# PART6_Connectors.net
KiCad netlist of a schematic drawn in Altium Designer
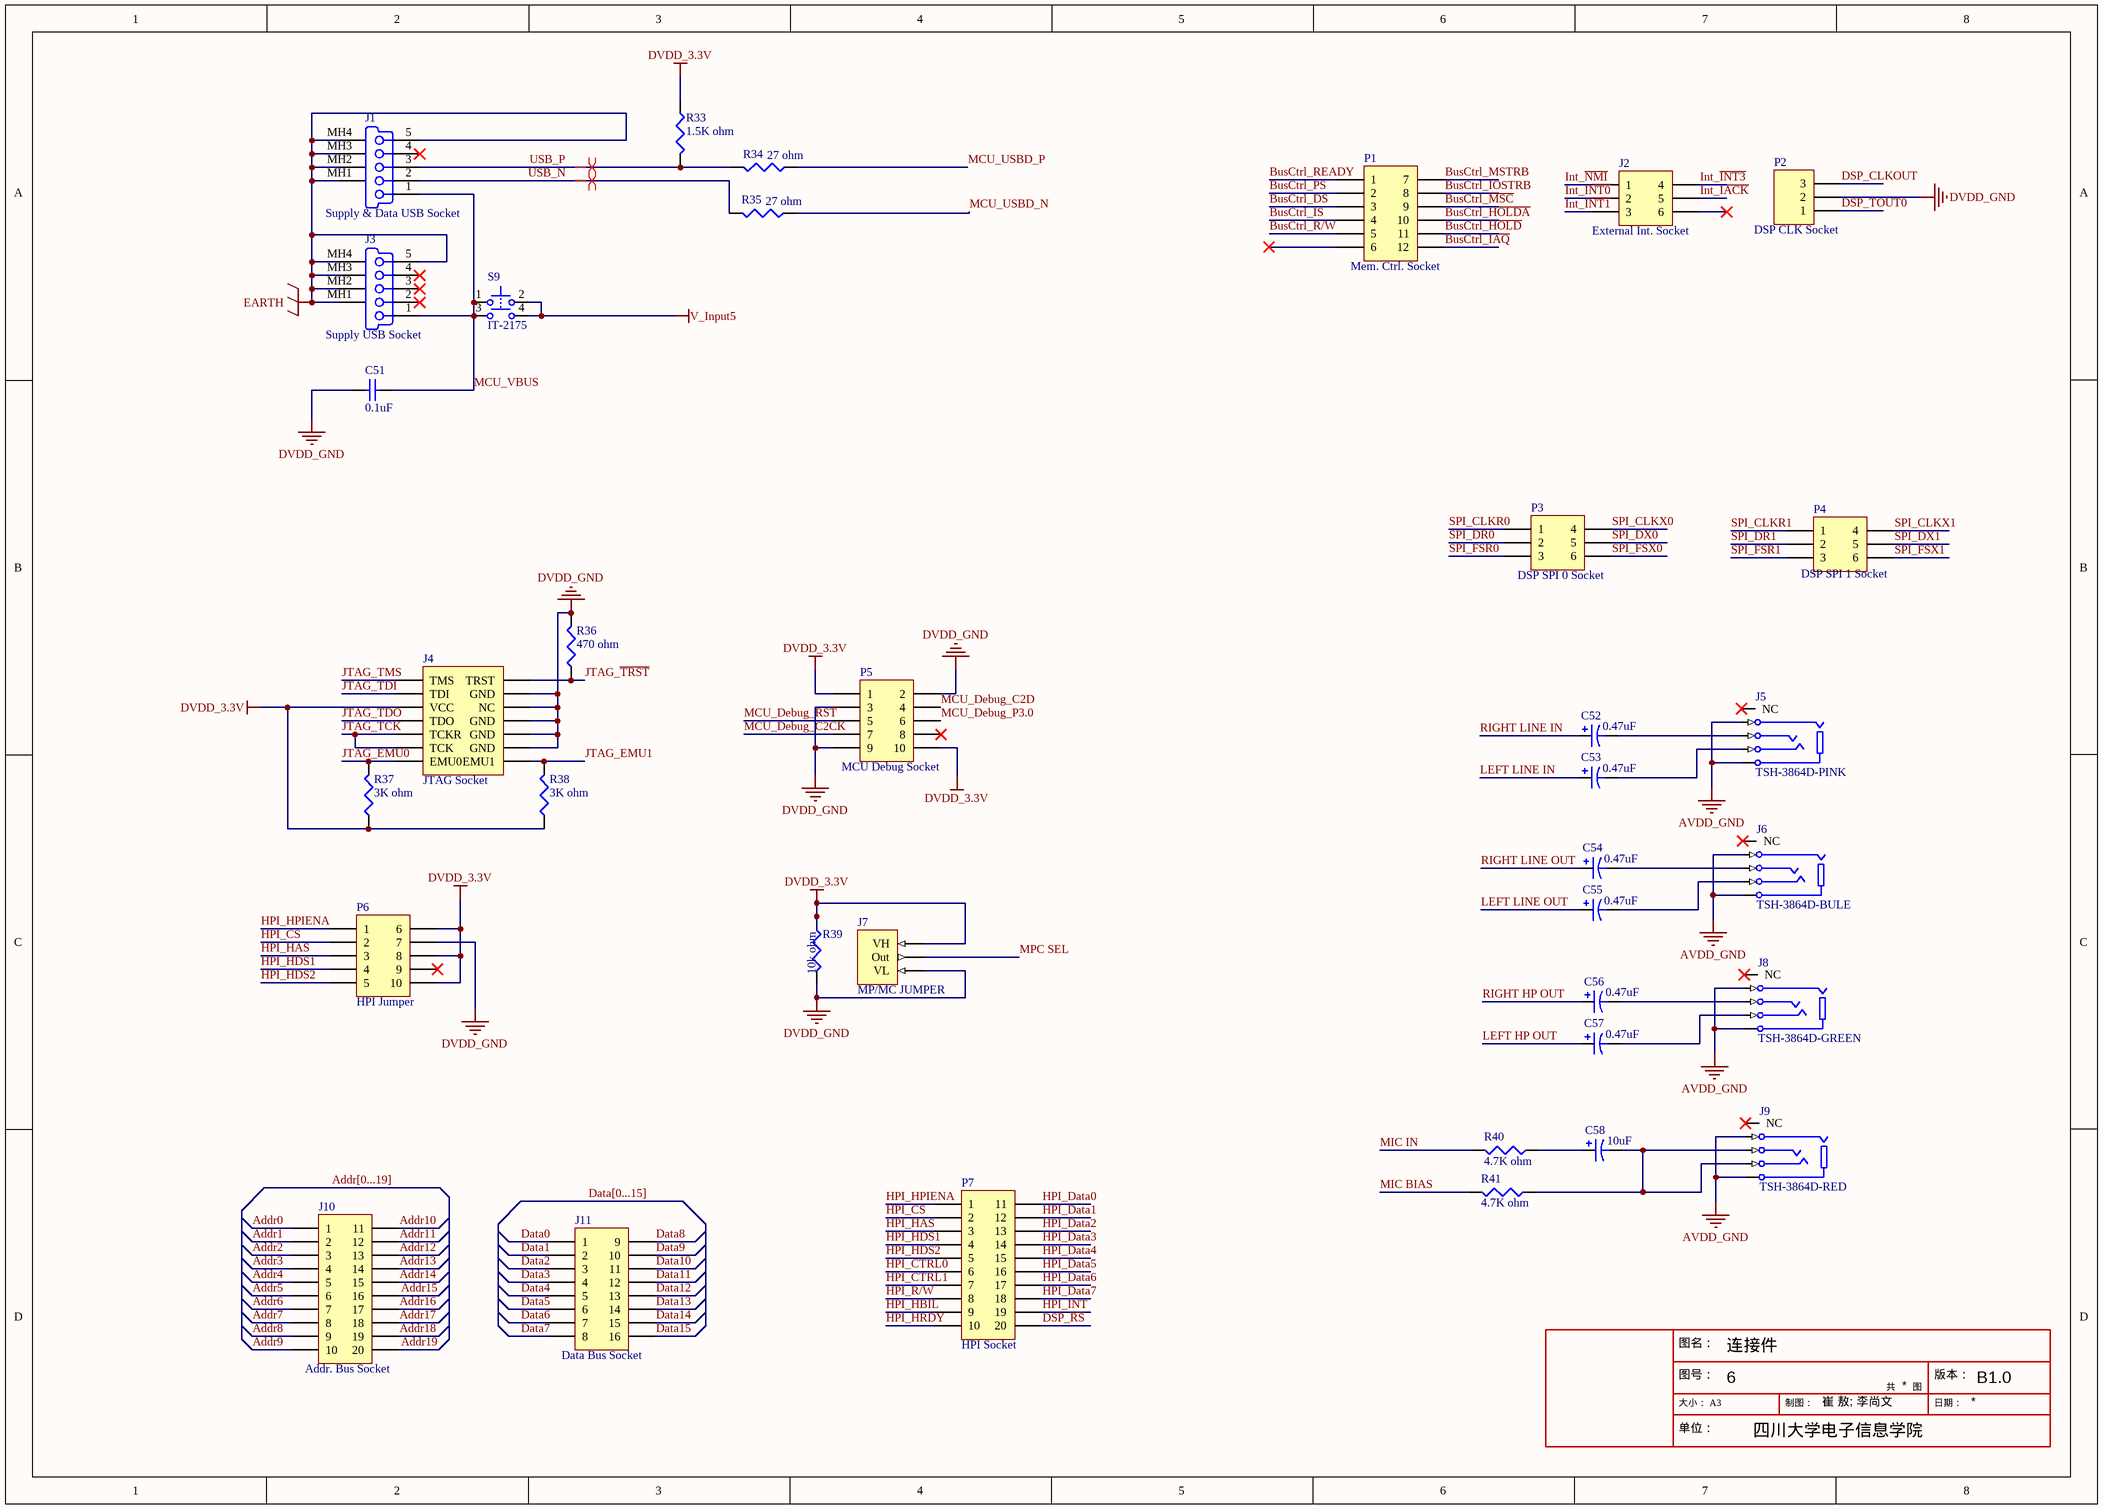
[diagram p0: PART6_Connectors.SchDoc]

(export (version "E")
  (design (tool "Eeschema 10.0.6"))
  (components
    (comp (ref "C51")
      (value "0.1uF")
      (footprint "1608[0603]")
      (description "贴片电容 1608")
      (fields (field (name "Comment") "Cap Semi") (field (name "PUBLISHER") "Altium Limited"))
      (libsource (lib "Miscellaneous Devices") (part "Cap Semi"))
    )
    (comp (ref "C52")
      (value "0.47uF")
      (footprint "C0805")
      (description "贴片钽电容 C0805")
      (fields (field (name "Comment") "Cap Tan") (field (name "PUBLISHER") "Altium Limited"))
      (libsource (lib "Miscellaneous Devices") (part "Cap Pol3"))
    )
    (comp (ref "C53")
      (value "0.47uF")
      (footprint "C0805")
      (description "贴片钽电容 C0805")
      (fields (field (name "Comment") "Cap Tan") (field (name "PUBLISHER") "Altium Limited"))
      (libsource (lib "Miscellaneous Devices") (part "Cap Pol3"))
    )
    (comp (ref "C54")
      (value "0.47uF")
      (footprint "C0805")
      (description "贴片钽电容 C0805")
      (fields (field (name "Comment") "Cap Tan") (field (name "PUBLISHER") "Altium Limited"))
      (libsource (lib "Miscellaneous Devices") (part "Cap Pol3"))
    )
    (comp (ref "C55")
      (value "0.47uF")
      (footprint "C0805")
      (description "贴片钽电容 C0805")
      (fields (field (name "Comment") "Cap Tan") (field (name "PUBLISHER") "Altium Limited"))
      (libsource (lib "Miscellaneous Devices") (part "Cap Pol3"))
    )
    (comp (ref "C56")
      (value "0.47uF")
      (footprint "C0805")
      (description "贴片钽电容 C0805")
      (fields (field (name "Comment") "Cap Tan") (field (name "PUBLISHER") "Altium Limited"))
      (libsource (lib "Miscellaneous Devices") (part "Cap Pol3"))
    )
    (comp (ref "C57")
      (value "0.47uF")
      (footprint "C0805")
      (description "贴片钽电容 C0805")
      (fields (field (name "Comment") "Cap Tan") (field (name "PUBLISHER") "Altium Limited"))
      (libsource (lib "Miscellaneous Devices") (part "Cap Pol3"))
    )
    (comp (ref "C58")
      (value "10uF")
      (footprint "C0805")
      (description "贴片钽电容 C0805")
      (fields (field (name "Comment") "Cap Tan") (field (name "PUBLISHER") "Altium Limited"))
      (libsource (lib "Miscellaneous Devices") (part "Cap Pol3"))
    )
    (comp (ref "J1")
      (value "Supply & Data USB Socket")
      (footprint "481900001")
      (fields (field (name "PUBLISHER") "Altium Limited"))
      (libsource (lib "Molex Serial Bus Mini USB") (part "0481900001"))
    )
    (comp (ref "J2")
      (value "External Int. Socket")
      (footprint "HDR2X3_CEN")
      (description "Header, 3-Pin, Dual row")
      (fields (field (name "PUBLISHER") "Altium Limited"))
      (libsource (lib "Miscellaneous Connectors") (part "Header 3X2A"))
    )
    (comp (ref "J3")
      (value "Supply USB Socket")
      (footprint "481900001")
      (fields (field (name "PUBLISHER") "Altium Limited"))
      (libsource (lib "Molex Serial Bus Mini USB") (part "0481900001"))
    )
    (comp (ref "J4")
      (value "JTAG Socket")
      (footprint "HDR2X7")
      (description "Header, 7-Pin, Dual row")
      (fields (field (name "PUBLISHER") "Altium Limited"))
      (libsource (lib "TMS320VC5401") (part "JTAG 14PIN CONN"))
    )
    (comp (ref "J5")
      (value "TSH-3864D-PINK")
      (footprint "PJ-386D")
      (description "Phone Jack, PJ-386D Series, Right Angle, SM, 4-Conductor Open Circuit")
      (fields (field (name "PUBLISHER") "Altium Limited"))
      (libsource (lib "Contact Technology Phone Jack") (part "TSH-3864D"))
    )
    (comp (ref "J6")
      (value "TSH-3864D-BULE")
      (footprint "PJ-386D")
      (description "Phone Jack, PJ-386D Series, Right Angle, SM, 4-Conductor Open Circuit")
      (fields (field (name "PUBLISHER") "Altium Limited"))
      (libsource (lib "Contact Technology Phone Jack") (part "TSH-3864D"))
    )
    (comp (ref "J7")
      (value "MP/MC JUMPER")
      (footprint "HDR1X3")
      (description "Header, 3-Pin")
      (fields (field (name "PUBLISHER") "Altium Limited"))
      (libsource (lib "Miscellaneous Connectors") (part "Header 3"))
    )
    (comp (ref "J8")
      (value "TSH-3864D-GREEN")
      (footprint "PJ-386D")
      (description "Phone Jack, PJ-386D Series, Right Angle, SM, 4-Conductor Open Circuit")
      (fields (field (name "PUBLISHER") "Altium Limited"))
      (libsource (lib "Contact Technology Phone Jack") (part "TSH-3864D"))
    )
    (comp (ref "J9")
      (value "TSH-3864D-RED")
      (footprint "PJ-386D")
      (description "Phone Jack, PJ-386D Series, Right Angle, SM, 4-Conductor Open Circuit")
      (fields (field (name "PUBLISHER") "Altium Limited"))
      (libsource (lib "Contact Technology Phone Jack") (part "TSH-3864D"))
    )
    (comp (ref "J10")
      (value "Addr. Bus Socket")
      (footprint "HDR2X10_CEN")
      (description "Header, 10-Pin, Dual row")
      (fields (field (name "PUBLISHER") "Altium Limited"))
      (libsource (lib "Miscellaneous Connectors") (part "Header 10X2A"))
    )
    (comp (ref "J11")
      (value "Data Bus Socket")
      (footprint "HDR2X8_CEN")
      (description "Header, 8-Pin, Dual row")
      (fields (field (name "PUBLISHER") "Altium Limited"))
      (libsource (lib "Miscellaneous Connectors") (part "Header 8X2A"))
    )
    (comp (ref "P1")
      (value "Mem. Ctrl. Socket")
      (footprint "HDR2X6_CEN")
      (description "Header, 6-Pin, Dual row")
      (fields (field (name "PUBLISHER") "Altium Limited"))
      (libsource (lib "Miscellaneous Connectors") (part "Header 6X2A"))
    )
    (comp (ref "P2")
      (value "DSP CLK Socket")
      (footprint "HDR1X3")
      (description "Header, 3-Pin")
      (fields (field (name "PUBLISHER") "Altium Limited"))
      (libsource (lib "Miscellaneous Connectors") (part "Header 3"))
    )
    (comp (ref "P3")
      (value "DSP SPI 0 Socket")
      (footprint "HDR2X3_CEN")
      (description "Header, 3-Pin, Dual row")
      (fields (field (name "PUBLISHER") "Altium Limited"))
      (libsource (lib "Miscellaneous Connectors") (part "Header 3X2A"))
    )
    (comp (ref "P4")
      (value "DSP SPI 1 Socket")
      (footprint "HDR2X3_CEN")
      (description "Header, 3-Pin, Dual row")
      (fields (field (name "PUBLISHER") "Altium Limited"))
      (libsource (lib "Miscellaneous Connectors") (part "Header 3X2A"))
    )
    (comp (ref "P5")
      (value "MCU Debug Socket")
      (footprint "HDR2X5")
      (description "Header, 5-Pin, Dual row")
      (fields (field (name "PUBLISHER") "Altium Limited"))
      (libsource (lib "Miscellaneous Connectors") (part "Header 5X2"))
    )
    (comp (ref "P6")
      (value "HPI Jumper")
      (footprint "HDR2X5_CEN")
      (description "Header, 5-Pin, Dual row")
      (fields (field (name "PUBLISHER") "Altium Limited"))
      (libsource (lib "Miscellaneous Connectors") (part "Header 5X2A"))
    )
    (comp (ref "P7")
      (value "HPI Socket")
      (footprint "HDR2X10_CEN")
      (description "Header, 10-Pin, Dual row")
      (fields (field (name "PUBLISHER") "Altium Limited"))
      (libsource (lib "Miscellaneous Connectors") (part "Header 10X2A"))
    )
    (comp (ref "R33")
      (value "1.5K ohm")
      (footprint "J1-0603")
      (description "贴片电阻 0603")
      (fields (field (name "Comment") "Res3") (field (name "PUBLISHER") "Altium Limited"))
      (libsource (lib "Miscellaneous Devices") (part "Res3"))
    )
    (comp (ref "R34")
      (value "27 ohm")
      (footprint "J1-0603")
      (description "贴片电阻 0603")
      (fields (field (name "Comment") "Res3") (field (name "PUBLISHER") "Altium Limited"))
      (libsource (lib "Miscellaneous Devices") (part "Res3"))
    )
    (comp (ref "R35")
      (value "27 ohm")
      (footprint "J1-0603")
      (description "贴片电阻 0603")
      (fields (field (name "Comment") "Res3") (field (name "PUBLISHER") "Altium Limited"))
      (libsource (lib "Miscellaneous Devices") (part "Res3"))
    )
    (comp (ref "R36")
      (value "470 ohm")
      (footprint "J1-0603")
      (description "贴片电阻 0603")
      (fields (field (name "Comment") "Res3") (field (name "PUBLISHER") "Altium Limited"))
      (libsource (lib "Miscellaneous Devices") (part "Res3"))
    )
    (comp (ref "R37")
      (value "3K ohm")
      (footprint "J1-0603")
      (description "贴片电阻 0603")
      (fields (field (name "Comment") "Res3") (field (name "PUBLISHER") "Altium Limited"))
      (libsource (lib "Miscellaneous Devices") (part "Res3"))
    )
    (comp (ref "R38")
      (value "3K ohm")
      (footprint "J1-0603")
      (description "贴片电阻 0603")
      (fields (field (name "Comment") "Res3") (field (name "PUBLISHER") "Altium Limited"))
      (libsource (lib "Miscellaneous Devices") (part "Res3"))
    )
    (comp (ref "R39")
      (value "10k ohm")
      (footprint "J1-0603")
      (description "贴片电阻 0603")
      (fields (field (name "Comment") "Res3") (field (name "PUBLISHER") "Altium Limited"))
      (libsource (lib "Miscellaneous Devices") (part "Res3"))
    )
    (comp (ref "R40")
      (value "4.7K ohm")
      (footprint "J1-0603")
      (description "贴片电阻 0603")
      (fields (field (name "Comment") "Res3") (field (name "PUBLISHER") "Altium Limited"))
      (libsource (lib "Miscellaneous Devices") (part "Res3"))
    )
    (comp (ref "R41")
      (value "4.7K ohm")
      (footprint "J1-0603")
      (description "贴片电阻 0603")
      (fields (field (name "Comment") "Res3") (field (name "PUBLISHER") "Altium Limited"))
      (libsource (lib "Miscellaneous Devices") (part "Res3"))
    )
    (comp (ref "S9")
      (value "IT-2175")
      (footprint "IT-2175")
      (description "Tactile Switch, DPST; Thru-Hole; Vertical; Rating DC 12V, 50mA (max)")
      (fields (field (name "PUBLISHER") "Altium Limited"))
      (libsource (lib "IL Switch Push Button") (part "IT-2175"))
    )
  )
  (nets
    (net (code "3") (name "/Addr0") (class "Default")
      (node (ref "J10") (pin "1") (pinfunction "1_1") (pintype "passive"))
    )
    (net (code "4") (name "/Addr1") (class "Default")
      (node (ref "J10") (pin "2") (pinfunction "2_2") (pintype "passive"))
    )
    (net (code "5") (name "/Addr2") (class "Default")
      (node (ref "J10") (pin "3") (pinfunction "3_3") (pintype "passive"))
    )
    (net (code "6") (name "/Addr3") (class "Default")
      (node (ref "J10") (pin "4") (pinfunction "4_4") (pintype "passive"))
    )
    (net (code "7") (name "/Addr4") (class "Default")
      (node (ref "J10") (pin "5") (pinfunction "5_5") (pintype "passive"))
    )
    (net (code "8") (name "/Addr5") (class "Default")
      (node (ref "J10") (pin "6") (pinfunction "6_6") (pintype "passive"))
    )
    (net (code "9") (name "/Addr6") (class "Default")
      (node (ref "J10") (pin "7") (pinfunction "7_7") (pintype "passive"))
    )
    (net (code "10") (name "/Addr7") (class "Default")
      (node (ref "J10") (pin "8") (pinfunction "8_8") (pintype "passive"))
    )
    (net (code "11") (name "/Addr8") (class "Default")
      (node (ref "J10") (pin "9") (pinfunction "9_9") (pintype "passive"))
    )
    (net (code "12") (name "/Addr9") (class "Default")
      (node (ref "J10") (pin "10") (pinfunction "10_10") (pintype "passive"))
    )
    (net (code "13") (name "/Addr10") (class "Default")
      (node (ref "J10") (pin "11") (pinfunction "11_11") (pintype "passive"))
    )
    (net (code "14") (name "/Addr11") (class "Default")
      (node (ref "J10") (pin "12") (pinfunction "12_12") (pintype "passive"))
    )
    (net (code "15") (name "/Addr12") (class "Default")
      (node (ref "J10") (pin "13") (pinfunction "13_13") (pintype "passive"))
    )
    (net (code "16") (name "/Addr13") (class "Default")
      (node (ref "J10") (pin "14") (pinfunction "14_14") (pintype "passive"))
    )
    (net (code "17") (name "/Addr14") (class "Default")
      (node (ref "J10") (pin "15") (pinfunction "15_15") (pintype "passive"))
    )
    (net (code "18") (name "/Addr15") (class "Default")
      (node (ref "J10") (pin "16") (pinfunction "16_16") (pintype "passive"))
    )
    (net (code "19") (name "/Addr16") (class "Default")
      (node (ref "J10") (pin "17") (pinfunction "17_17") (pintype "passive"))
    )
    (net (code "20") (name "/Addr17") (class "Default")
      (node (ref "J10") (pin "18") (pinfunction "18_18") (pintype "passive"))
    )
    (net (code "21") (name "/Addr18") (class "Default")
      (node (ref "J10") (pin "19") (pinfunction "19_19") (pintype "passive"))
    )
    (net (code "22") (name "/Addr19") (class "Default")
      (node (ref "J10") (pin "20") (pinfunction "20_20") (pintype "passive"))
    )
    (net (code "23") (name "/BusCtrl_IOSTRB") (class "Default")
      (node (ref "P1") (pin "8") (pinfunction "8_8") (pintype "passive"))
    )
    (net (code "24") (name "/BusCtrl_MSTRB") (class "Default")
      (node (ref "P1") (pin "7") (pinfunction "7_7") (pintype "passive"))
    )
    (net (code "25") (name "/BusCtrl_READY") (class "Default")
      (node (ref "P1") (pin "1") (pinfunction "1_1") (pintype "passive"))
    )
    (net (code "26") (name "/BusCtrl_R{slash}~{W}") (class "Default")
      (node (ref "P1") (pin "5") (pinfunction "5_5") (pintype "passive"))
    )
    (net (code "27") (name "/BusCtrl_~{DS}") (class "Default")
      (node (ref "P1") (pin "3") (pinfunction "3_3") (pintype "passive"))
    )
    (net (code "28") (name "/BusCtrl_~{HOLDA}") (class "Default")
      (node (ref "P1") (pin "10") (pinfunction "10_10") (pintype "passive"))
    )
    (net (code "29") (name "/BusCtrl_~{HOLD}") (class "Default")
      (node (ref "P1") (pin "11") (pinfunction "11_11") (pintype "passive"))
    )
    (net (code "30") (name "/BusCtrl_~{IAQ}") (class "Default")
      (node (ref "P1") (pin "12") (pinfunction "12_12") (pintype "passive"))
    )
    (net (code "31") (name "/BusCtrl_~{IS}") (class "Default")
      (node (ref "P1") (pin "4") (pinfunction "4_4") (pintype "passive"))
    )
    (net (code "32") (name "/BusCtrl_~{MSC}") (class "Default")
      (node (ref "P1") (pin "9") (pinfunction "9_9") (pintype "passive"))
    )
    (net (code "33") (name "/BusCtrl_~{PS}") (class "Default")
      (node (ref "P1") (pin "2") (pinfunction "2_2") (pintype "passive"))
    )
    (net (code "34") (name "/DSP_CLKOUT") (class "Default")
      (node (ref "P2") (pin "3") (pinfunction "VH_3") (pintype "input"))
    )
    (net (code "35") (name "/DSP_TOUT0") (class "Default")
      (node (ref "P2") (pin "1") (pinfunction "VL_1") (pintype "input"))
    )
    (net (code "36") (name "/DSP_~{RS}") (class "Default")
      (node (ref "P7") (pin "20") (pinfunction "20_20") (pintype "passive"))
    )
    (net (code "37") (name "/Data0") (class "Default")
      (node (ref "J11") (pin "1") (pinfunction "1_1") (pintype "passive"))
    )
    (net (code "38") (name "/Data1") (class "Default")
      (node (ref "J11") (pin "2") (pinfunction "2_2") (pintype "passive"))
    )
    (net (code "39") (name "/Data2") (class "Default")
      (node (ref "J11") (pin "3") (pinfunction "3_3") (pintype "passive"))
    )
    (net (code "40") (name "/Data3") (class "Default")
      (node (ref "J11") (pin "4") (pinfunction "4_4") (pintype "passive"))
    )
    (net (code "41") (name "/Data4") (class "Default")
      (node (ref "J11") (pin "5") (pinfunction "5_5") (pintype "passive"))
    )
    (net (code "42") (name "/Data5") (class "Default")
      (node (ref "J11") (pin "6") (pinfunction "6_6") (pintype "passive"))
    )
    (net (code "43") (name "/Data6") (class "Default")
      (node (ref "J11") (pin "7") (pinfunction "7_7") (pintype "passive"))
    )
    (net (code "44") (name "/Data7") (class "Default")
      (node (ref "J11") (pin "8") (pinfunction "8_8") (pintype "passive"))
    )
    (net (code "45") (name "/Data8") (class "Default")
      (node (ref "J11") (pin "9") (pinfunction "9_9") (pintype "passive"))
    )
    (net (code "46") (name "/Data9") (class "Default")
      (node (ref "J11") (pin "10") (pinfunction "10_10") (pintype "passive"))
    )
    (net (code "47") (name "/Data10") (class "Default")
      (node (ref "J11") (pin "11") (pinfunction "11_11") (pintype "passive"))
    )
    (net (code "48") (name "/Data11") (class "Default")
      (node (ref "J11") (pin "12") (pinfunction "12_12") (pintype "passive"))
    )
    (net (code "49") (name "/Data12") (class "Default")
      (node (ref "J11") (pin "13") (pinfunction "13_13") (pintype "passive"))
    )
    (net (code "50") (name "/Data13") (class "Default")
      (node (ref "J11") (pin "14") (pinfunction "14_14") (pintype "passive"))
    )
    (net (code "51") (name "/Data14") (class "Default")
      (node (ref "J11") (pin "15") (pinfunction "15_15") (pintype "passive"))
    )
    (net (code "52") (name "/Data15") (class "Default")
      (node (ref "J11") (pin "16") (pinfunction "16_16") (pintype "passive"))
    )
    (net (code "53") (name "/HPI_CTRL0") (class "Default")
      (node (ref "P7") (pin "6") (pinfunction "6_6") (pintype "passive"))
    )
    (net (code "54") (name "/HPI_CTRL1") (class "Default")
      (node (ref "P7") (pin "7") (pinfunction "7_7") (pintype "passive"))
    )
    (net (code "55") (name "/HPI_Data0") (class "Default")
      (node (ref "P7") (pin "11") (pinfunction "11_11") (pintype "passive"))
    )
    (net (code "56") (name "/HPI_Data1") (class "Default")
      (node (ref "P7") (pin "12") (pinfunction "12_12") (pintype "passive"))
    )
    (net (code "57") (name "/HPI_Data2") (class "Default")
      (node (ref "P7") (pin "13") (pinfunction "13_13") (pintype "passive"))
    )
    (net (code "58") (name "/HPI_Data3") (class "Default")
      (node (ref "P7") (pin "14") (pinfunction "14_14") (pintype "passive"))
    )
    (net (code "59") (name "/HPI_Data4") (class "Default")
      (node (ref "P7") (pin "15") (pinfunction "15_15") (pintype "passive"))
    )
    (net (code "60") (name "/HPI_Data5") (class "Default")
      (node (ref "P7") (pin "16") (pinfunction "16_16") (pintype "passive"))
    )
    (net (code "61") (name "/HPI_Data6") (class "Default")
      (node (ref "P7") (pin "17") (pinfunction "17_17") (pintype "passive"))
    )
    (net (code "62") (name "/HPI_Data7") (class "Default")
      (node (ref "P7") (pin "18") (pinfunction "18_18") (pintype "passive"))
    )
    (net (code "63") (name "/HPI_HBIL") (class "Default")
      (node (ref "P7") (pin "9") (pinfunction "9_9") (pintype "passive"))
    )
    (net (code "64") (name "/HPI_HPIENA") (class "Default")
      (node (ref "P6") (pin "1") (pinfunction "1_1") (pintype "passive"))
      (node (ref "P7") (pin "1") (pinfunction "1_1") (pintype "passive"))
    )
    (net (code "65") (name "/HPI_HRDY") (class "Default")
      (node (ref "P7") (pin "10") (pinfunction "10_10") (pintype "passive"))
    )
    (net (code "66") (name "/HPI_INT") (class "Default")
      (node (ref "P7") (pin "19") (pinfunction "19_19") (pintype "passive"))
    )
    (net (code "67") (name "/HPI_R{slash}~{W}") (class "Default")
      (node (ref "P7") (pin "8") (pinfunction "8_8") (pintype "passive"))
    )
    (net (code "68") (name "/HPI_~{CS}") (class "Default")
      (node (ref "P6") (pin "2") (pinfunction "2_2") (pintype "passive"))
      (node (ref "P7") (pin "2") (pinfunction "2_2") (pintype "passive"))
    )
    (net (code "69") (name "/HPI_~{HAS}") (class "Default")
      (node (ref "P6") (pin "3") (pinfunction "3_3") (pintype "passive"))
      (node (ref "P7") (pin "3") (pinfunction "3_3") (pintype "passive"))
    )
    (net (code "70") (name "/HPI_~{HDS1}") (class "Default")
      (node (ref "P6") (pin "4") (pinfunction "4_4") (pintype "passive"))
      (node (ref "P7") (pin "4") (pinfunction "4_4") (pintype "passive"))
    )
    (net (code "71") (name "/HPI_~{HDS2}") (class "Default")
      (node (ref "P6") (pin "5") (pinfunction "5_5") (pintype "passive"))
      (node (ref "P7") (pin "5") (pinfunction "5_5") (pintype "passive"))
    )
    (net (code "72") (name "/Int_~{IACK}") (class "Default")
      (node (ref "J2") (pin "5") (pinfunction "5_5") (pintype "passive"))
    )
    (net (code "73") (name "/Int_~{INT0}") (class "Default")
      (node (ref "J2") (pin "2") (pinfunction "2_2") (pintype "passive"))
    )
    (net (code "74") (name "/Int_~{INT1}") (class "Default")
      (node (ref "J2") (pin "3") (pinfunction "3_3") (pintype "passive"))
    )
    (net (code "75") (name "/Int_~{INT3}") (class "Default")
      (node (ref "J2") (pin "4") (pinfunction "4_4") (pintype "passive"))
    )
    (net (code "76") (name "/Int_~{NMI}") (class "Default")
      (node (ref "J2") (pin "1") (pinfunction "1_1") (pintype "passive"))
    )
    (net (code "77") (name "/JTAG_EMU0") (class "Default")
      (node (ref "J4") (pin "13") (pinfunction "EMU0_13") (pintype "passive"))
      (node (ref "R37") (pin "2") (pinfunction "2_2") (pintype "passive"))
    )
    (net (code "78") (name "/JTAG_EMU1") (class "Default")
      (node (ref "J4") (pin "14") (pinfunction "EMU1_14") (pintype "passive"))
      (node (ref "R38") (pin "2") (pinfunction "2_2") (pintype "passive"))
    )
    (net (code "79") (name "/JTAG_TCK") (class "Default")
      (node (ref "J4") (pin "11") (pinfunction "TCK_11") (pintype "passive"))
      (node (ref "J4") (pin "9") (pinfunction "TCKR_9") (pintype "passive"))
    )
    (net (code "80") (name "/JTAG_TDI") (class "Default")
      (node (ref "J4") (pin "3") (pinfunction "TDI_3") (pintype "passive"))
    )
    (net (code "81") (name "/JTAG_TDO") (class "Default")
      (node (ref "J4") (pin "7") (pinfunction "TDO_7") (pintype "passive"))
    )
    (net (code "82") (name "/JTAG_TMS") (class "Default")
      (node (ref "J4") (pin "1") (pinfunction "TMS_1") (pintype "passive"))
    )
    (net (code "83") (name "/JTAG_~{TRST}") (class "Default")
      (node (ref "J4") (pin "2") (pinfunction "TRST_2") (pintype "passive"))
      (node (ref "R36") (pin "1") (pinfunction "1_1") (pintype "passive"))
    )
    (net (code "84") (name "/LEFT HP OUT") (class "Default")
      (node (ref "C57") (pin "1") (pinfunction "1_1") (pintype "passive"))
    )
    (net (code "85") (name "/LEFT LINE IN") (class "Default")
      (node (ref "C53") (pin "1") (pinfunction "1_1") (pintype "passive"))
    )
    (net (code "86") (name "/LEFT LINE OUT") (class "Default")
      (node (ref "C55") (pin "1") (pinfunction "1_1") (pintype "passive"))
    )
    (net (code "87") (name "/MCU_Debug_C2CK") (class "Default")
      (node (ref "P5") (pin "7") (pinfunction "7_7") (pintype "passive"))
    )
    (net (code "88") (name "/MCU_Debug_C2D") (class "Default")
      (node (ref "P5") (pin "4") (pinfunction "4_4") (pintype "passive"))
    )
    (net (code "89") (name "/MCU_Debug_P3.0") (class "Default")
      (node (ref "P5") (pin "6") (pinfunction "6_6") (pintype "passive"))
    )
    (net (code "90") (name "/MCU_Debug_~{RST}") (class "Default")
      (node (ref "P5") (pin "5") (pinfunction "5_5") (pintype "passive"))
    )
    (net (code "91") (name "/MCU_USBD_N") (class "Default")
      (node (ref "R35") (pin "1") (pinfunction "1_1") (pintype "passive"))
    )
    (net (code "92") (name "/MCU_USBD_P") (class "Default")
      (node (ref "R34") (pin "1") (pinfunction "1_1") (pintype "passive"))
    )
    (net (code "93") (name "/MCU_VBUS") (class "Default")
      (node (ref "C51") (pin "2") (pinfunction "2_2") (pintype "passive"))
      (node (ref "J1") (pin "1") (pinfunction "V_BUS_(5V)_1") (pintype "passive"))
      (node (ref "J3") (pin "1") (pinfunction "V_BUS_(5V)_1") (pintype "passive"))
      (node (ref "S9") (pin "1") (pinfunction "1_1") (pintype "passive"))
      (node (ref "S9") (pin "3") (pinfunction "3_3") (pintype "passive"))
    )
    (net (code "94") (name "/MIC BIAS") (class "Default")
      (node (ref "R41") (pin "2") (pinfunction "2_2") (pintype "passive"))
    )
    (net (code "95") (name "/MIC IN") (class "Default")
      (node (ref "R40") (pin "2") (pinfunction "2_2") (pintype "passive"))
    )
    (net (code "96") (name "/MPC SEL") (class "Default")
      (node (ref "J7") (pin "2") (pinfunction "Out_2") (pintype "output"))
    )
    (net (code "97") (name "/RIGHT HP OUT") (class "Default")
      (node (ref "C56") (pin "1") (pinfunction "1_1") (pintype "passive"))
    )
    (net (code "98") (name "/RIGHT LINE IN") (class "Default")
      (node (ref "C52") (pin "1") (pinfunction "1_1") (pintype "passive"))
    )
    (net (code "99") (name "/RIGHT LINE OUT") (class "Default")
      (node (ref "C54") (pin "1") (pinfunction "1_1") (pintype "passive"))
    )
    (net (code "100") (name "/SPI_CLKR0") (class "Default")
      (node (ref "P3") (pin "1") (pinfunction "1_1") (pintype "passive"))
    )
    (net (code "101") (name "/SPI_CLKR1") (class "Default")
      (node (ref "P4") (pin "1") (pinfunction "1_1") (pintype "passive"))
    )
    (net (code "102") (name "/SPI_CLKX0") (class "Default")
      (node (ref "P3") (pin "4") (pinfunction "4_4") (pintype "passive"))
    )
    (net (code "103") (name "/SPI_CLKX1") (class "Default")
      (node (ref "P4") (pin "4") (pinfunction "4_4") (pintype "passive"))
    )
    (net (code "104") (name "/SPI_DR0") (class "Default")
      (node (ref "P3") (pin "2") (pinfunction "2_2") (pintype "passive"))
    )
    (net (code "105") (name "/SPI_DR1") (class "Default")
      (node (ref "P4") (pin "2") (pinfunction "2_2") (pintype "passive"))
    )
    (net (code "106") (name "/SPI_DX0") (class "Default")
      (node (ref "P3") (pin "5") (pinfunction "5_5") (pintype "passive"))
    )
    (net (code "107") (name "/SPI_DX1") (class "Default")
      (node (ref "P4") (pin "5") (pinfunction "5_5") (pintype "passive"))
    )
    (net (code "108") (name "/SPI_FSR0") (class "Default")
      (node (ref "P3") (pin "3") (pinfunction "3_3") (pintype "passive"))
    )
    (net (code "109") (name "/SPI_FSR1") (class "Default")
      (node (ref "P4") (pin "3") (pinfunction "3_3") (pintype "passive"))
    )
    (net (code "110") (name "/SPI_FSX0") (class "Default")
      (node (ref "P3") (pin "6") (pinfunction "6_6") (pintype "passive"))
    )
    (net (code "111") (name "/SPI_FSX1") (class "Default")
      (node (ref "P4") (pin "6") (pinfunction "6_6") (pintype "passive"))
    )
    (net (code "112") (name "/USB_N") (class "Default")
      (node (ref "J1") (pin "2") (pinfunction "D-_2") (pintype "passive"))
      (node (ref "R35") (pin "2") (pinfunction "2_2") (pintype "passive"))
    )
    (net (code "113") (name "/USB_P") (class "Default")
      (node (ref "J1") (pin "3") (pinfunction "D+_3") (pintype "passive"))
      (node (ref "R33") (pin "2") (pinfunction "2_2") (pintype "passive"))
      (node (ref "R34") (pin "2") (pinfunction "2_2") (pintype "passive"))
    )
    (net (code "116") (name "AVDD_GND") (class "Default")
      (node (ref "J5") (pin "1") (pinfunction "S_1") (pintype "power_in"))
      (node (ref "J5") (pin "4") (pinfunction "SN_4") (pintype "input"))
      (node (ref "J6") (pin "1") (pinfunction "S_1") (pintype "power_in"))
      (node (ref "J6") (pin "4") (pinfunction "SN_4") (pintype "input"))
      (node (ref "J8") (pin "1") (pinfunction "S_1") (pintype "power_in"))
      (node (ref "J8") (pin "4") (pinfunction "SN_4") (pintype "input"))
      (node (ref "J9") (pin "1") (pinfunction "S_1") (pintype "power_in"))
      (node (ref "J9") (pin "4") (pinfunction "SN_4") (pintype "input"))
    )
    (net (code "117") (name "DVDD_3.3V") (class "Default")
      (node (ref "J4") (pin "5") (pinfunction "VCC_5") (pintype "passive"))
      (node (ref "J7") (pin "3") (pinfunction "VH_3") (pintype "input"))
      (node (ref "P5") (pin "1") (pinfunction "1_1") (pintype "passive"))
      (node (ref "P5") (pin "10") (pinfunction "10_10") (pintype "passive"))
      (node (ref "P6") (pin "10") (pinfunction "10_10") (pintype "passive"))
      (node (ref "P6") (pin "6") (pinfunction "6_6") (pintype "passive"))
      (node (ref "P6") (pin "8") (pinfunction "8_8") (pintype "passive"))
      (node (ref "R33") (pin "1") (pinfunction "1_1") (pintype "passive"))
      (node (ref "R37") (pin "1") (pinfunction "1_1") (pintype "passive"))
      (node (ref "R38") (pin "1") (pinfunction "1_1") (pintype "passive"))
      (node (ref "R39") (pin "1") (pinfunction "1_1") (pintype "passive"))
    )
    (net (code "118") (name "DVDD_GND") (class "Default")
      (node (ref "C51") (pin "1") (pinfunction "1_1") (pintype "passive"))
      (node (ref "J4") (pin "10") (pinfunction "GND_10") (pintype "passive"))
      (node (ref "J4") (pin "12") (pinfunction "GND_12") (pintype "passive"))
      (node (ref "J4") (pin "4") (pinfunction "GND_4") (pintype "passive"))
      (node (ref "J4") (pin "6") (pinfunction "NC_6") (pintype "passive"))
      (node (ref "J4") (pin "8") (pinfunction "GND_8") (pintype "passive"))
      (node (ref "J7") (pin "1") (pinfunction "VL_1") (pintype "input"))
      (node (ref "P2") (pin "2") (pinfunction "Out_2") (pintype "output"))
      (node (ref "P5") (pin "2") (pinfunction "2_2") (pintype "passive"))
      (node (ref "P5") (pin "3") (pinfunction "3_3") (pintype "passive"))
      (node (ref "P5") (pin "9") (pinfunction "9_9") (pintype "passive"))
      (node (ref "P6") (pin "7") (pinfunction "7_7") (pintype "passive"))
      (node (ref "R36") (pin "2") (pinfunction "2_2") (pintype "passive"))
      (node (ref "R39") (pin "2") (pinfunction "2_2") (pintype "passive"))
    )
    (net (code "119") (name "EARTH") (class "Default")
      (node (ref "J1") (pin "5") (pinfunction "GND_5") (pintype "passive"))
      (node (ref "J1") (pin "MH1") (pinfunction "Tab_MH1") (pintype "passive"))
      (node (ref "J1") (pin "MH2") (pinfunction "Tab_MH2") (pintype "passive"))
      (node (ref "J1") (pin "MH3") (pinfunction "Tab_MH3") (pintype "passive"))
      (node (ref "J1") (pin "MH4") (pinfunction "Tab_MH4") (pintype "passive"))
      (node (ref "J3") (pin "5") (pinfunction "GND_5") (pintype "passive"))
      (node (ref "J3") (pin "MH1") (pinfunction "Tab_MH1") (pintype "passive"))
      (node (ref "J3") (pin "MH2") (pinfunction "Tab_MH2") (pintype "passive"))
      (node (ref "J3") (pin "MH3") (pinfunction "Tab_MH3") (pintype "passive"))
      (node (ref "J3") (pin "MH4") (pinfunction "Tab_MH4") (pintype "passive"))
    )
    (net (code "120") (name "Net-(C58-Pad1)") (class "Default")
      (node (ref "C58") (pin "1") (pinfunction "1_1") (pintype "passive"))
      (node (ref "R40") (pin "1") (pinfunction "1_1") (pintype "passive"))
    )
    (net (code "121") (name "Net-(J5-R)") (class "Default")
      (node (ref "C53") (pin "2") (pinfunction "2_2") (pintype "passive"))
      (node (ref "J5") (pin "3") (pinfunction "R_3") (pintype "input"))
    )
    (net (code "122") (name "Net-(J5-T)") (class "Default")
      (node (ref "C52") (pin "2") (pinfunction "2_2") (pintype "passive"))
      (node (ref "J5") (pin "2") (pinfunction "T_2") (pintype "input"))
    )
    (net (code "123") (name "Net-(J6-R)") (class "Default")
      (node (ref "C55") (pin "2") (pinfunction "2_2") (pintype "passive"))
      (node (ref "J6") (pin "3") (pinfunction "R_3") (pintype "input"))
    )
    (net (code "124") (name "Net-(J6-T)") (class "Default")
      (node (ref "C54") (pin "2") (pinfunction "2_2") (pintype "passive"))
      (node (ref "J6") (pin "2") (pinfunction "T_2") (pintype "input"))
    )
    (net (code "125") (name "Net-(J8-R)") (class "Default")
      (node (ref "C57") (pin "2") (pinfunction "2_2") (pintype "passive"))
      (node (ref "J8") (pin "3") (pinfunction "R_3") (pintype "input"))
    )
    (net (code "126") (name "Net-(J8-T)") (class "Default")
      (node (ref "C56") (pin "2") (pinfunction "2_2") (pintype "passive"))
      (node (ref "J8") (pin "2") (pinfunction "T_2") (pintype "input"))
    )
    (net (code "127") (name "Net-(J9-R)") (class "Default")
      (node (ref "C58") (pin "2") (pinfunction "2_2") (pintype "passive"))
      (node (ref "J9") (pin "2") (pinfunction "T_2") (pintype "input"))
      (node (ref "J9") (pin "3") (pinfunction "R_3") (pintype "input"))
      (node (ref "R41") (pin "1") (pinfunction "1_1") (pintype "passive"))
    )
    (net (code "128") (name "V_Input5") (class "Default")
      (node (ref "S9") (pin "2") (pinfunction "2_2") (pintype "passive"))
      (node (ref "S9") (pin "4") (pinfunction "4_4") (pintype "passive"))
    )
    (net (code "129") (name "unconnected-(J1-NC-Pad4)") (class "Default")
      (node (ref "J1") (pin "4") (pinfunction "NC_4") (pintype "passive+no_connect"))
    )
    (net (code "130") (name "unconnected-(J2-Pad6)") (class "Default")
      (node (ref "J2") (pin "6") (pinfunction "6_6") (pintype "passive+no_connect"))
    )
    (net (code "131") (name "unconnected-(J3-D+-Pad3)") (class "Default")
      (node (ref "J3") (pin "3") (pinfunction "D+_3") (pintype "passive+no_connect"))
    )
    (net (code "132") (name "unconnected-(J3-D--Pad2)") (class "Default")
      (node (ref "J3") (pin "2") (pinfunction "D-_2") (pintype "passive+no_connect"))
    )
    (net (code "133") (name "unconnected-(J3-NC-Pad4)") (class "Default")
      (node (ref "J3") (pin "4") (pinfunction "NC_4") (pintype "passive+no_connect"))
    )
    (net (code "134") (name "unconnected-(J5-NC-Pad10)") (class "Default")
      (node (ref "J5") (pin "10") (pinfunction "NC_10") (pintype "passive+no_connect"))
    )
    (net (code "135") (name "unconnected-(J6-NC-Pad10)") (class "Default")
      (node (ref "J6") (pin "10") (pinfunction "NC_10") (pintype "passive+no_connect"))
    )
    (net (code "136") (name "unconnected-(J8-NC-Pad10)") (class "Default")
      (node (ref "J8") (pin "10") (pinfunction "NC_10") (pintype "passive+no_connect"))
    )
    (net (code "137") (name "unconnected-(J9-NC-Pad10)") (class "Default")
      (node (ref "J9") (pin "10") (pinfunction "NC_10") (pintype "passive+no_connect"))
    )
    (net (code "138") (name "unconnected-(P1-Pad6)") (class "Default")
      (node (ref "P1") (pin "6") (pinfunction "6_6") (pintype "passive+no_connect"))
    )
    (net (code "139") (name "unconnected-(P5-Pad8)") (class "Default")
      (node (ref "P5") (pin "8") (pinfunction "8_8") (pintype "passive+no_connect"))
    )
    (net (code "140") (name "unconnected-(P6-Pad9)") (class "Default")
      (node (ref "P6") (pin "9") (pinfunction "9_9") (pintype "passive+no_connect"))
    )
  )
)
